# Heated_Bed_New.net
KiCad netlist of a schematic drawn in EAGLE
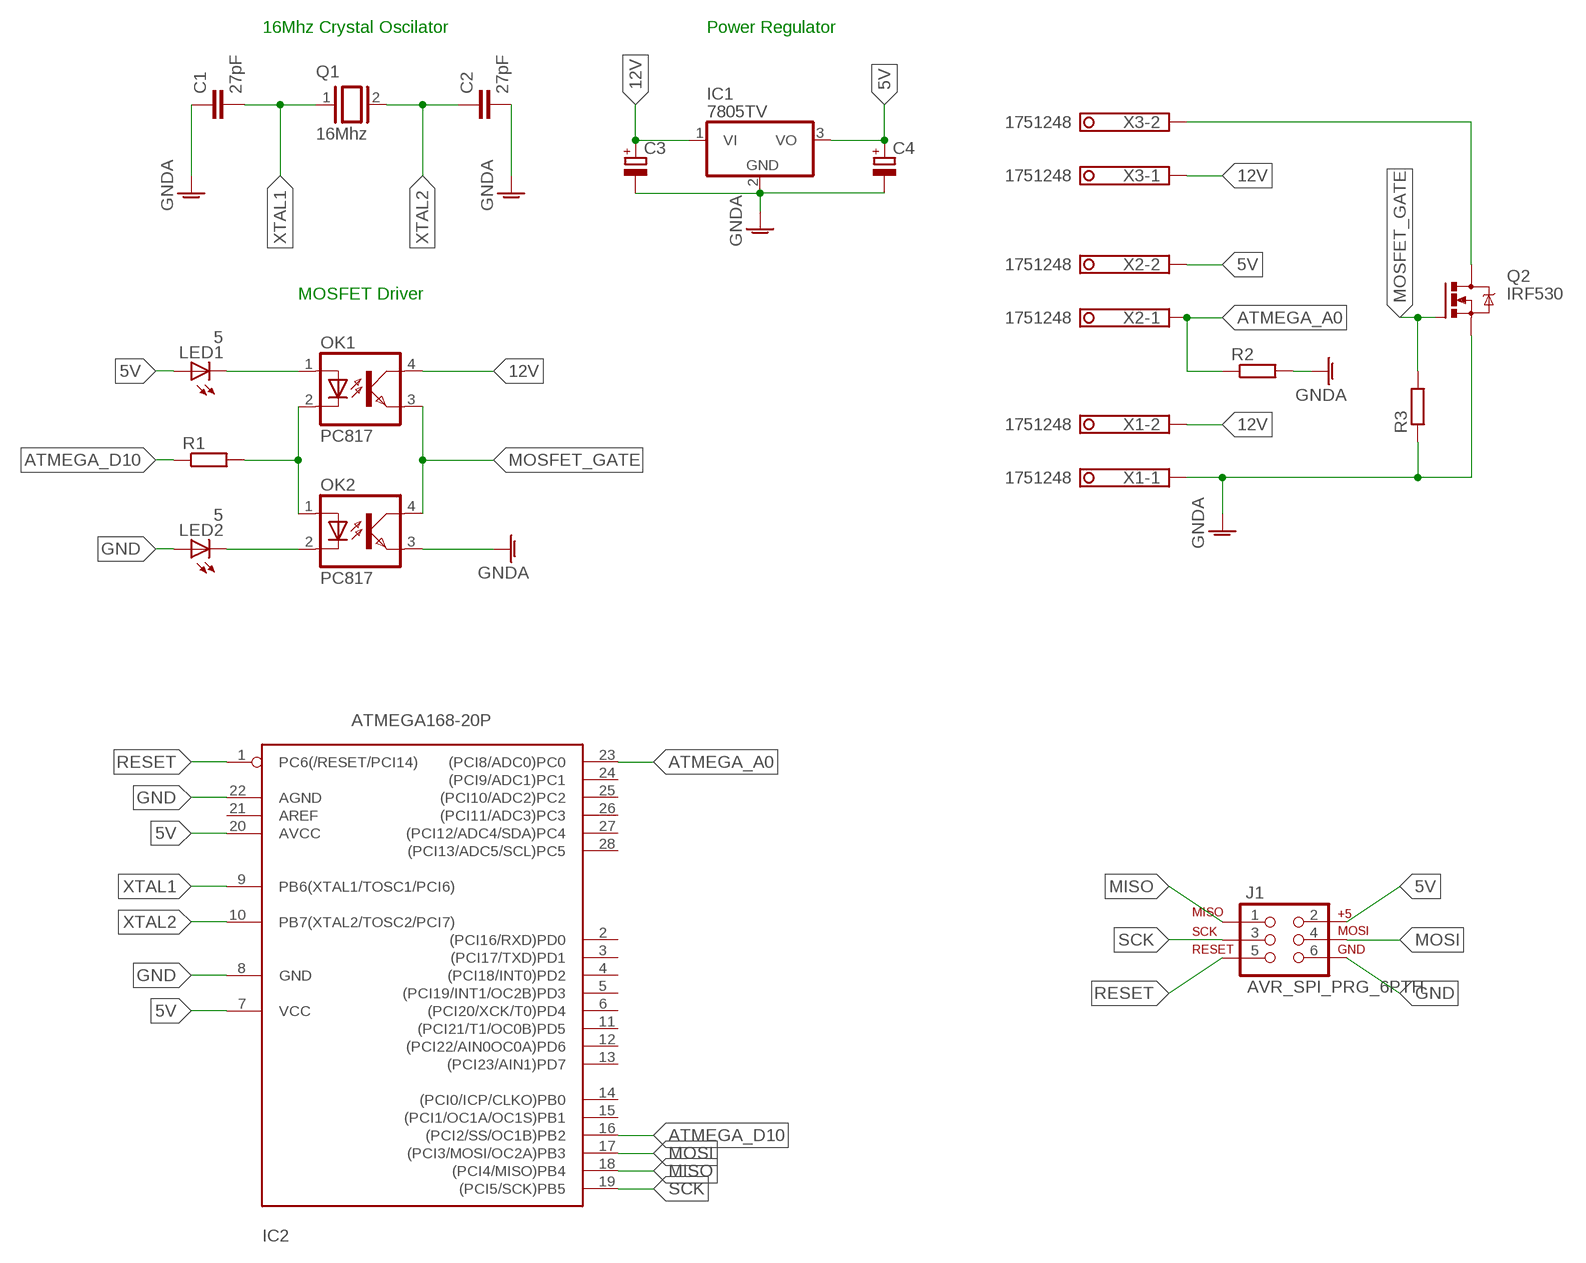
[diagram p0: schematic, sheet 1]

(export (version "E")
  (design (tool "Eeschema 10.0.6"))
  (components
    (comp (ref "C1")
      (value "27pF")
      (footprint "eagle-import:C025-025X050")
      (libsource (lib "eagle-import") (part "C-EU025-025X050"))
    )
    (comp (ref "C2")
      (value "27pF")
      (footprint "eagle-import:C025-025X050")
      (libsource (lib "eagle-import") (part "C-EU025-025X050"))
    )
    (comp (ref "C3")
      (value "CPOL-EUE5-10.5")
      (footprint "eagle-import:E5-10,5")
      (libsource (lib "eagle-import") (part "CPOL-EUE5-10.5"))
    )
    (comp (ref "C4")
      (value "CPOL-EUE5-10.5")
      (footprint "eagle-import:E5-10,5")
      (libsource (lib "eagle-import") (part "CPOL-EUE5-10.5"))
    )
    (comp (ref "IC1")
      (value "7805TV")
      (footprint "eagle-import:TO220V")
      (libsource (lib "eagle-import") (part "78TV05"))
    )
    (comp (ref "IC2")
      (value "ATMEGA168-20P")
      (footprint "eagle-import:DIL28-3")
      (libsource (lib "eagle-import") (part "ATMEGA168P-20"))
    )
    (comp (ref "J1")
      (value "AVR_SPI_PRG_6PTH")
      (footprint "eagle-import:2X3")
      (libsource (lib "eagle-import") (part "AVR_SPI_PRG_6PTH"))
    )
    (comp (ref "LED1")
      (value "5")
      (footprint "eagle-import:LED5MM")
      (libsource (lib "eagle-import") (part "LED5MM"))
    )
    (comp (ref "LED2")
      (value "5")
      (footprint "eagle-import:LED5MM")
      (libsource (lib "eagle-import") (part "LED5MM"))
    )
    (comp (ref "OK1")
      (value "PC817")
      (footprint "eagle-import:DIL04")
      (fields (field (name "MPN") "PC817X4J000F"))
      (libsource (lib "eagle-import") (part "PC817"))
    )
    (comp (ref "OK2")
      (value "PC817")
      (footprint "eagle-import:DIL04")
      (fields (field (name "MPN") "PC817X4J000F"))
      (libsource (lib "eagle-import") (part "PC817"))
    )
    (comp (ref "Q1")
      (value "16Mhz")
      (footprint "eagle-import:QS")
      (libsource (lib "eagle-import") (part "XTAL/S"))
    )
    (comp (ref "Q2")
      (value "IRF530")
      (footprint "eagle-import:TO220BV")
      (libsource (lib "eagle-import") (part "IRF530"))
    )
    (comp (ref "R1")
      (value "R-EU_0207/7")
      (footprint "eagle-import:0207_7")
      (libsource (lib "eagle-import") (part "R-EU_0207/7"))
    )
    (comp (ref "R2")
      (value "R-EU_0207/7")
      (footprint "eagle-import:0207_7")
      (libsource (lib "eagle-import") (part "R-EU_0207/7"))
    )
    (comp (ref "R3")
      (value "R-EU_0207/7")
      (footprint "eagle-import:0207_7")
      (libsource (lib "eagle-import") (part "R-EU_0207/7"))
    )
    (comp (ref "X1")
      (value "1751248")
      (footprint "eagle-import:1751248")
      (libsource (lib "eagle-import") (part "1751248"))
    )
    (comp (ref "X2")
      (value "1751248")
      (footprint "eagle-import:1751248")
      (libsource (lib "eagle-import") (part "1751248"))
    )
    (comp (ref "X3")
      (value "1751248")
      (footprint "eagle-import:1751248")
      (libsource (lib "eagle-import") (part "1751248"))
    )
  )
  (nets
    (net (code "1") (name "5V") (class "Default")
      (node (ref "C4") (pin "+") (pinfunction "+_+") (pintype "passive"))
      (node (ref "IC1") (pin "3") (pinfunction "VO_3") (pintype "passive"))
      (node (ref "IC2") (pin "20") (pinfunction "AVCC_20") (pintype "bidirectional"))
      (node (ref "IC2") (pin "7") (pinfunction "VCC_7") (pintype "bidirectional"))
      (node (ref "J1") (pin "2") (pinfunction "2_2") (pintype "passive"))
      (node (ref "LED1") (pin "A") (pinfunction "A_A") (pintype "passive"))
      (node (ref "X2") (pin "2") (pinfunction "K_2") (pintype "passive"))
    )
    (net (code "2") (name "12V") (class "Default")
      (node (ref "C3") (pin "+") (pinfunction "+_+") (pintype "passive"))
      (node (ref "IC1") (pin "1") (pinfunction "VI_1") (pintype "input"))
      (node (ref "OK1") (pin "4") (pinfunction "COL_4") (pintype "passive"))
      (node (ref "X1") (pin "2") (pinfunction "K_2") (pintype "passive"))
      (node (ref "X3") (pin "1") (pinfunction "K_1") (pintype "passive"))
    )
    (net (code "3") (name "ATMEGA_A0") (class "Default")
      (node (ref "IC2") (pin "23") (pinfunction "(PCI8/ADC0)PC0_23") (pintype "bidirectional"))
      (node (ref "R2") (pin "1") (pinfunction "1_1") (pintype "passive"))
      (node (ref "X2") (pin "1") (pinfunction "K_1") (pintype "passive"))
    )
    (net (code "4") (name "ATMEGA_D10") (class "Default")
      (node (ref "IC2") (pin "16") (pinfunction "(PCI2/SS/OC1B)PB2_16") (pintype "bidirectional"))
      (node (ref "R1") (pin "1") (pinfunction "1_1") (pintype "passive"))
    )
    (net (code "5") (name "GND") (class "Default")
      (node (ref "C1") (pin "1") (pinfunction "1_1") (pintype "passive"))
      (node (ref "C2") (pin "2") (pinfunction "2_2") (pintype "passive"))
      (node (ref "C3") (pin "-") (pinfunction "-_-") (pintype "passive"))
      (node (ref "C4") (pin "-") (pinfunction "-_-") (pintype "passive"))
      (node (ref "IC1") (pin "2") (pinfunction "GND_2") (pintype "passive"))
      (node (ref "IC2") (pin "22") (pinfunction "AGND_22") (pintype "bidirectional"))
      (node (ref "IC2") (pin "8") (pinfunction "GND_8") (pintype "bidirectional"))
      (node (ref "J1") (pin "6") (pinfunction "6_6") (pintype "passive"))
      (node (ref "LED2") (pin "A") (pinfunction "A_A") (pintype "passive"))
      (node (ref "OK2") (pin "3") (pinfunction "EMIT_3") (pintype "passive"))
      (node (ref "Q2") (pin "S") (pinfunction "S_S") (pintype "passive"))
      (node (ref "R2") (pin "2") (pinfunction "2_2") (pintype "passive"))
      (node (ref "R3") (pin "1") (pinfunction "1_1") (pintype "passive"))
      (node (ref "X1") (pin "1") (pinfunction "K_1") (pintype "passive"))
    )
    (net (code "6") (name "MISO") (class "Default")
      (node (ref "IC2") (pin "18") (pinfunction "(PCI4/MISO)PB4_18") (pintype "bidirectional"))
      (node (ref "J1") (pin "1") (pinfunction "1_1") (pintype "passive"))
    )
    (net (code "7") (name "MOSFET_GATE") (class "Default")
      (node (ref "OK1") (pin "3") (pinfunction "EMIT_3") (pintype "passive"))
      (node (ref "OK2") (pin "4") (pinfunction "COL_4") (pintype "passive"))
      (node (ref "Q2") (pin "G") (pinfunction "G_G") (pintype "passive"))
      (node (ref "R3") (pin "2") (pinfunction "2_2") (pintype "passive"))
    )
    (net (code "8") (name "MOSI") (class "Default")
      (node (ref "IC2") (pin "17") (pinfunction "(PCI3/MOSI/OC2A)PB3_17") (pintype "bidirectional"))
      (node (ref "J1") (pin "4") (pinfunction "4_4") (pintype "passive"))
    )
    (net (code "9") (name "Net-(LED1-C)") (class "Default")
      (node (ref "LED1") (pin "K") (pinfunction "C_K") (pintype "passive"))
      (node (ref "OK1") (pin "1") (pinfunction "A_1") (pintype "passive"))
    )
    (net (code "10") (name "Net-(LED2-C)") (class "Default")
      (node (ref "LED2") (pin "K") (pinfunction "C_K") (pintype "passive"))
      (node (ref "OK2") (pin "2") (pinfunction "C_2") (pintype "passive"))
    )
    (net (code "11") (name "Net-(OK1-C)") (class "Default")
      (node (ref "OK1") (pin "2") (pinfunction "C_2") (pintype "passive"))
      (node (ref "OK2") (pin "1") (pinfunction "A_1") (pintype "passive"))
      (node (ref "R1") (pin "2") (pinfunction "2_2") (pintype "passive"))
    )
    (net (code "12") (name "Net-(X3B-K)") (class "Default")
      (node (ref "Q2") (pin "D") (pinfunction "D_D") (pintype "passive"))
      (node (ref "X3") (pin "2") (pinfunction "K_2") (pintype "passive"))
    )
    (net (code "13") (name "RESET") (class "Default")
      (node (ref "IC2") (pin "1") (pinfunction "PC6(/RESET/PCI14)_1") (pintype "bidirectional"))
      (node (ref "J1") (pin "5") (pinfunction "5_5") (pintype "passive"))
    )
    (net (code "14") (name "SCK") (class "Default")
      (node (ref "IC2") (pin "19") (pinfunction "(PCI5/SCK)PB5_19") (pintype "bidirectional"))
      (node (ref "J1") (pin "3") (pinfunction "3_3") (pintype "passive"))
    )
    (net (code "15") (name "XTAL1") (class "Default")
      (node (ref "C1") (pin "2") (pinfunction "2_2") (pintype "passive"))
      (node (ref "IC2") (pin "9") (pinfunction "PB6(XTAL1/TOSC1/PCI6)_9") (pintype "bidirectional"))
      (node (ref "Q1") (pin "1") (pinfunction "1_1") (pintype "passive"))
    )
    (net (code "16") (name "XTAL2") (class "Default")
      (node (ref "C2") (pin "1") (pinfunction "1_1") (pintype "passive"))
      (node (ref "IC2") (pin "10") (pinfunction "PB7(XTAL2/TOSC2/PCI7)_10") (pintype "bidirectional"))
      (node (ref "Q1") (pin "2") (pinfunction "2_2") (pintype "passive"))
    )
    (net (code "17") (name "unconnected-(IC2-(PCI0{slash}ICP{slash}CLKO)PB0-Pad14)") (class "Default")
      (node (ref "IC2") (pin "14") (pinfunction "(PCI0/ICP/CLKO)PB0_14") (pintype "bidirectional"))
    )
    (net (code "18") (name "unconnected-(IC2-(PCI1{slash}OC1A{slash}OC1S)PB1-Pad15)") (class "Default")
      (node (ref "IC2") (pin "15") (pinfunction "(PCI1/OC1A/OC1S)PB1_15") (pintype "bidirectional"))
    )
    (net (code "19") (name "unconnected-(IC2-(PCI9{slash}ADC1)PC1-Pad24)") (class "Default")
      (node (ref "IC2") (pin "24") (pinfunction "(PCI9/ADC1)PC1_24") (pintype "bidirectional"))
    )
    (net (code "20") (name "unconnected-(IC2-(PCI10{slash}ADC2)PC2-Pad25)") (class "Default")
      (node (ref "IC2") (pin "25") (pinfunction "(PCI10/ADC2)PC2_25") (pintype "bidirectional"))
    )
    (net (code "21") (name "unconnected-(IC2-(PCI11{slash}ADC3)PC3-Pad26)") (class "Default")
      (node (ref "IC2") (pin "26") (pinfunction "(PCI11/ADC3)PC3_26") (pintype "bidirectional"))
    )
    (net (code "22") (name "unconnected-(IC2-(PCI12{slash}ADC4{slash}SDA)PC4-Pad27)") (class "Default")
      (node (ref "IC2") (pin "27") (pinfunction "(PCI12/ADC4/SDA)PC4_27") (pintype "bidirectional"))
    )
    (net (code "23") (name "unconnected-(IC2-(PCI13{slash}ADC5{slash}SCL)PC5-Pad28)") (class "Default")
      (node (ref "IC2") (pin "28") (pinfunction "(PCI13/ADC5/SCL)PC5_28") (pintype "bidirectional"))
    )
    (net (code "24") (name "unconnected-(IC2-(PCI16{slash}RXD)PD0-Pad2)") (class "Default")
      (node (ref "IC2") (pin "2") (pinfunction "(PCI16/RXD)PD0_2") (pintype "bidirectional"))
    )
    (net (code "25") (name "unconnected-(IC2-(PCI17{slash}TXD)PD1-Pad3)") (class "Default")
      (node (ref "IC2") (pin "3") (pinfunction "(PCI17/TXD)PD1_3") (pintype "bidirectional"))
    )
    (net (code "26") (name "unconnected-(IC2-(PCI18{slash}INT0)PD2-Pad4)") (class "Default")
      (node (ref "IC2") (pin "4") (pinfunction "(PCI18/INT0)PD2_4") (pintype "bidirectional"))
    )
    (net (code "27") (name "unconnected-(IC2-(PCI19{slash}INT1{slash}OC2B)PD3-Pad5)") (class "Default")
      (node (ref "IC2") (pin "5") (pinfunction "(PCI19/INT1/OC2B)PD3_5") (pintype "bidirectional"))
    )
    (net (code "28") (name "unconnected-(IC2-(PCI20{slash}XCK{slash}T0)PD4-Pad6)") (class "Default")
      (node (ref "IC2") (pin "6") (pinfunction "(PCI20/XCK/T0)PD4_6") (pintype "bidirectional"))
    )
    (net (code "29") (name "unconnected-(IC2-(PCI21{slash}T1{slash}OC0B)PD5-Pad11)") (class "Default")
      (node (ref "IC2") (pin "11") (pinfunction "(PCI21/T1/OC0B)PD5_11") (pintype "bidirectional"))
    )
    (net (code "30") (name "unconnected-(IC2-(PCI22{slash}AIN0OC0A)PD6-Pad12)") (class "Default")
      (node (ref "IC2") (pin "12") (pinfunction "(PCI22/AIN0OC0A)PD6_12") (pintype "bidirectional"))
    )
    (net (code "31") (name "unconnected-(IC2-(PCI23{slash}AIN1)PD7-Pad13)") (class "Default")
      (node (ref "IC2") (pin "13") (pinfunction "(PCI23/AIN1)PD7_13") (pintype "bidirectional"))
    )
    (net (code "32") (name "unconnected-(IC2-AREF-Pad21)") (class "Default")
      (node (ref "IC2") (pin "21") (pinfunction "AREF_21") (pintype "bidirectional"))
    )
  )
)
